# alimentacao.net
KiCad netlist of a schematic drawn in Altium Designer
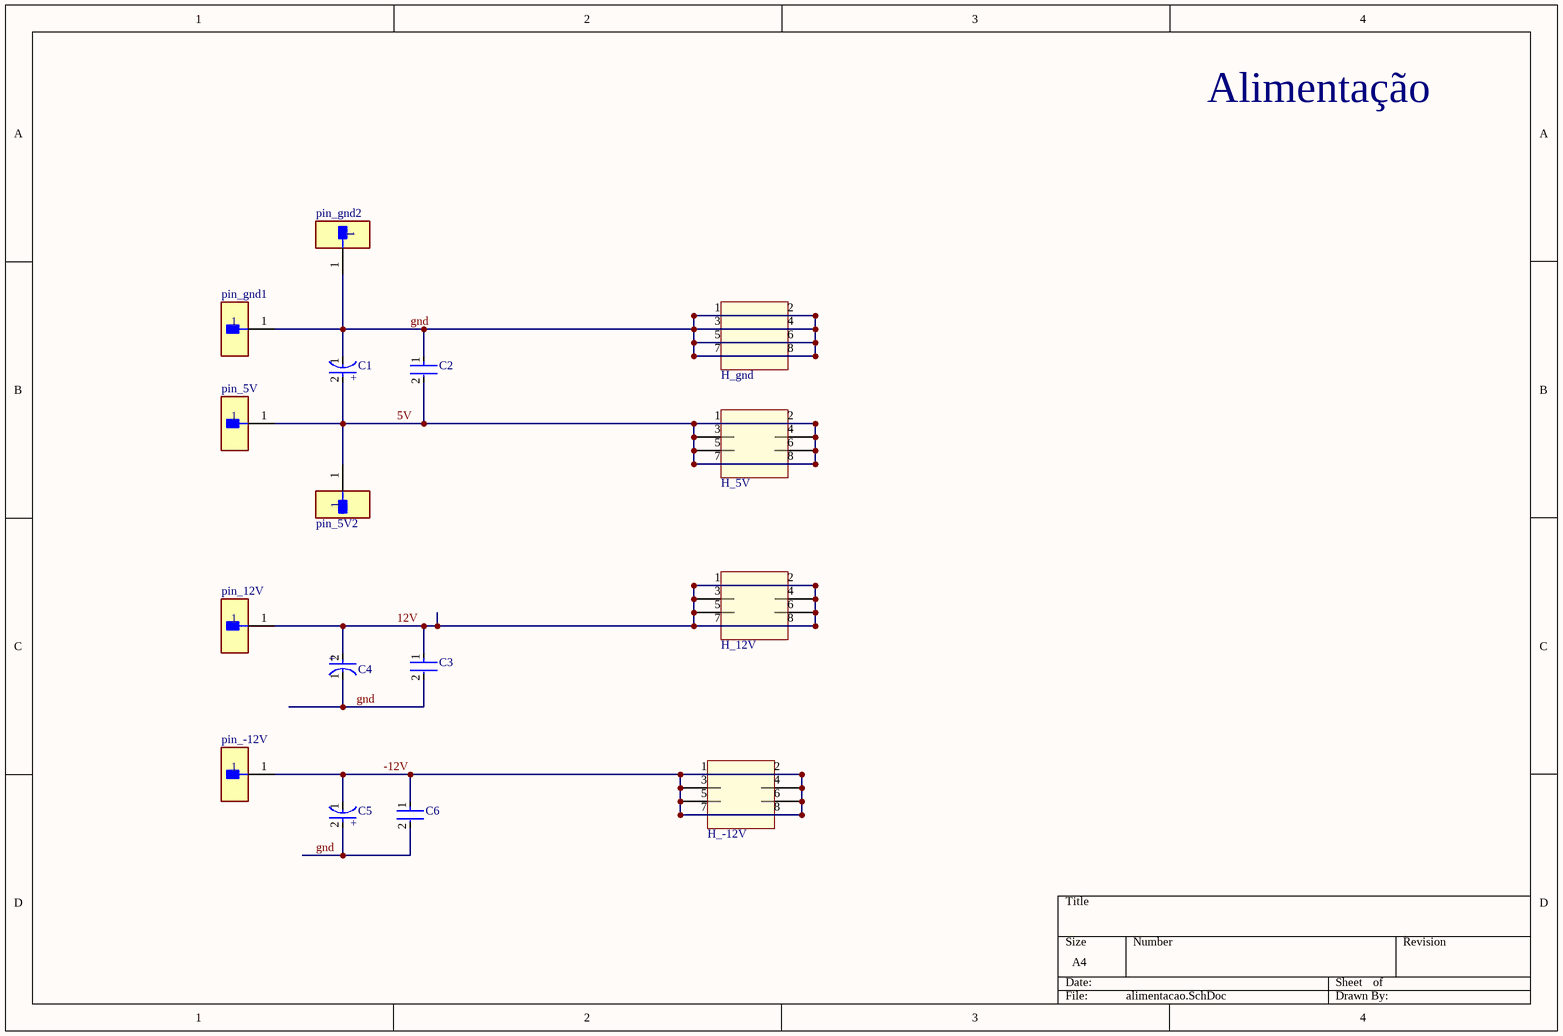
[diagram p0: alimentacao.SchDoc]

(export (version "E")
  (design (tool "Eeschema 10.0.6"))
  (components
    (comp (ref "C1")
      (value "EEU-FM1H101BJ")
      (footprint "FP-FM8-MFG")
      (description "CAP ALUM 100UF 20% 50V RADIAL")
      (fields (field (name "TOLERANCE") "20%"))
      (libsource (lib "Altium Content Vault") (part "203bc49f2ac43e59fd269a8c329ed05"))
    )
    (comp (ref "C2")
      (value "RCER71H335K3K1H03B")
      (footprint "FP-RCE3M1-MFG")
      (description "Cap Ceramic 3.3uF 50V X7R ±10% Radial 5mm +125°C Automotive Ammo Pack")
      (fields (field (name "TOLERANCE") "10%"))
      (libsource (lib "Altium Content Vault") (part "02cd4be3c70576c341d710602a673aa"))
    )
    (comp (ref "C3")
      (value "RCER71H335K3K1H03B")
      (footprint "FP-RCE3M1-MFG")
      (description "Cap Ceramic 3.3uF 50V X7R ±10% Radial 5mm +125°C Automotive Ammo Pack")
      (fields (field (name "TOLERANCE") "10%"))
      (libsource (lib "Altium Content Vault") (part "02cd4be3c70576c341d710602a673aa"))
    )
    (comp (ref "C4")
      (value "EEU-FM1H101BJ")
      (footprint "FP-FM8-MFG")
      (description "CAP ALUM 100UF 20% 50V RADIAL")
      (fields (field (name "TOLERANCE") "20%"))
      (libsource (lib "Altium Content Vault") (part "203bc49f2ac43e59fd269a8c329ed05"))
    )
    (comp (ref "C5")
      (value "EEU-FM1H101BJ")
      (footprint "FP-FM8-MFG")
      (description "CAP ALUM 100UF 20% 50V RADIAL")
      (fields (field (name "TOLERANCE") "20%"))
      (libsource (lib "Altium Content Vault") (part "203bc49f2ac43e59fd269a8c329ed05"))
    )
    (comp (ref "C6")
      (value "RCER71H335K3K1H03B")
      (footprint "FP-RCE3M1-MFG")
      (description "Cap Ceramic 3.3uF 50V X7R ±10% Radial 5mm +125°C Automotive Ammo Pack")
      (fields (field (name "TOLERANCE") "10%"))
      (libsource (lib "Altium Content Vault") (part "02cd4be3c70576c341d710602a673aa"))
    )
    (comp (ref "H_-12V")
      (value "header 2x4")
      (footprint "header 2x4")
      (description "header male 2x4")
      (libsource (lib "Schlib1") (part "header 2x4"))
    )
    (comp (ref "H_5V")
      (value "header 2x4")
      (footprint "header 2x4")
      (description "header male 2x4")
      (libsource (lib "Schlib1") (part "header 2x4"))
    )
    (comp (ref "H_12V")
      (value "header 2x4")
      (footprint "header 2x4")
      (description "header male 2x4")
      (libsource (lib "Schlib1") (part "header 2x4"))
    )
    (comp (ref "H_gnd")
      (value "header 2x4")
      (footprint "header 2x4")
      (description "header male 2x4")
      (libsource (lib "Schlib1") (part "header 2x4"))
    )
    (comp (ref "pin_-12V")
      (value "TSW-101-07-L-S")
      (footprint "FP-TSW-101-07-L-S-MFG")
      (description "CONN HEADER VERT 1POS")
      (libsource (lib "") (part "dd45045ce8184df9e99e12baf3f412c_1"))
    )
    (comp (ref "pin_5V")
      (value "TSW-101-07-L-S")
      (footprint "FP-TSW-101-07-L-S-MFG")
      (description "CONN HEADER VERT 1POS")
      (libsource (lib "") (part "dd45045ce8184df9e99e12baf3f412c_1"))
    )
    (comp (ref "pin_5V2")
      (value "TSW-101-07-L-S")
      (footprint "FP-TSW-101-07-L-S-MFG")
      (description "CONN HEADER VERT 1POS")
      (libsource (lib "") (part "dd45045ce8184df9e99e12baf3f412c_2"))
    )
    (comp (ref "pin_12V")
      (value "TSW-101-07-L-S")
      (footprint "FP-TSW-101-07-L-S-MFG")
      (description "CONN HEADER VERT 1POS")
      (libsource (lib "") (part "dd45045ce8184df9e99e12baf3f412c_1"))
    )
    (comp (ref "pin_gnd1")
      (value "TSW-101-07-L-S")
      (footprint "FP-TSW-101-07-L-S-MFG")
      (description "CONN HEADER VERT 1POS")
      (libsource (lib "") (part "dd45045ce8184df9e99e12baf3f412c_1"))
    )
    (comp (ref "pin_gnd2")
      (value "TSW-101-07-L-S")
      (footprint "FP-TSW-101-07-L-S-MFG")
      (description "CONN HEADER VERT 1POS")
      (libsource (lib "Altium Content Vault") (part "dd45045ce8184df9e99e12baf3f412c"))
    )
  )
  (nets
    (net (code "1") (name "/-12V") (class "Default")
      (node (ref "C5") (pin "1") (pinfunction "C_1") (pintype "passive"))
      (node (ref "C6") (pin "1") (pinfunction "1_1") (pintype "passive"))
      (node (ref "H_-12V") (pin "1") (pinfunction "1_1") (pintype "passive"))
      (node (ref "H_-12V") (pin "2") (pinfunction "2_2") (pintype "passive"))
      (node (ref "H_-12V") (pin "3") (pinfunction "3_3") (pintype "passive"))
      (node (ref "H_-12V") (pin "4") (pinfunction "4_4") (pintype "passive"))
      (node (ref "H_-12V") (pin "5") (pinfunction "5_5") (pintype "passive"))
      (node (ref "H_-12V") (pin "6") (pinfunction "6_6") (pintype "passive"))
      (node (ref "H_-12V") (pin "7") (pinfunction "7_7") (pintype "passive"))
      (node (ref "H_-12V") (pin "8") (pinfunction "8_8") (pintype "passive"))
      (node (ref "pin_-12V") (pin "1") (pinfunction "1_1") (pintype "passive"))
    )
    (net (code "2") (name "/5V") (class "Default")
      (node (ref "C1") (pin "2") (pinfunction "A_2") (pintype "passive"))
      (node (ref "C2") (pin "2") (pinfunction "2_2") (pintype "passive"))
      (node (ref "H_5V") (pin "1") (pinfunction "1_1") (pintype "passive"))
      (node (ref "H_5V") (pin "2") (pinfunction "2_2") (pintype "passive"))
      (node (ref "H_5V") (pin "3") (pinfunction "3_3") (pintype "passive"))
      (node (ref "H_5V") (pin "4") (pinfunction "4_4") (pintype "passive"))
      (node (ref "H_5V") (pin "5") (pinfunction "5_5") (pintype "passive"))
      (node (ref "H_5V") (pin "6") (pinfunction "6_6") (pintype "passive"))
      (node (ref "H_5V") (pin "7") (pinfunction "7_7") (pintype "passive"))
      (node (ref "H_5V") (pin "8") (pinfunction "8_8") (pintype "passive"))
      (node (ref "pin_5V") (pin "1") (pinfunction "1_1") (pintype "passive"))
      (node (ref "pin_5V2") (pin "1") (pinfunction "1_1") (pintype "passive"))
    )
    (net (code "3") (name "/12V") (class "Default")
      (node (ref "C3") (pin "1") (pinfunction "1_1") (pintype "passive"))
      (node (ref "C4") (pin "2") (pinfunction "A_2") (pintype "passive"))
      (node (ref "H_12V") (pin "1") (pinfunction "1_1") (pintype "passive"))
      (node (ref "H_12V") (pin "2") (pinfunction "2_2") (pintype "passive"))
      (node (ref "H_12V") (pin "3") (pinfunction "3_3") (pintype "passive"))
      (node (ref "H_12V") (pin "4") (pinfunction "4_4") (pintype "passive"))
      (node (ref "H_12V") (pin "5") (pinfunction "5_5") (pintype "passive"))
      (node (ref "H_12V") (pin "6") (pinfunction "6_6") (pintype "passive"))
      (node (ref "H_12V") (pin "7") (pinfunction "7_7") (pintype "passive"))
      (node (ref "H_12V") (pin "8") (pinfunction "8_8") (pintype "passive"))
      (node (ref "pin_12V") (pin "1") (pinfunction "1_1") (pintype "passive"))
    )
    (net (code "4") (name "/gnd") (class "Default")
      (node (ref "C1") (pin "1") (pinfunction "C_1") (pintype "passive"))
      (node (ref "C2") (pin "1") (pinfunction "1_1") (pintype "passive"))
      (node (ref "C3") (pin "2") (pinfunction "2_2") (pintype "passive"))
      (node (ref "C4") (pin "1") (pinfunction "C_1") (pintype "passive"))
      (node (ref "C5") (pin "2") (pinfunction "A_2") (pintype "passive"))
      (node (ref "C6") (pin "2") (pinfunction "2_2") (pintype "passive"))
      (node (ref "H_gnd") (pin "1") (pinfunction "1_1") (pintype "passive"))
      (node (ref "H_gnd") (pin "2") (pinfunction "2_2") (pintype "passive"))
      (node (ref "H_gnd") (pin "3") (pinfunction "3_3") (pintype "passive"))
      (node (ref "H_gnd") (pin "4") (pinfunction "4_4") (pintype "passive"))
      (node (ref "H_gnd") (pin "5") (pinfunction "5_5") (pintype "passive"))
      (node (ref "H_gnd") (pin "6") (pinfunction "6_6") (pintype "passive"))
      (node (ref "H_gnd") (pin "7") (pinfunction "7_7") (pintype "passive"))
      (node (ref "H_gnd") (pin "8") (pinfunction "8_8") (pintype "passive"))
      (node (ref "pin_gnd1") (pin "1") (pinfunction "1_1") (pintype "passive"))
      (node (ref "pin_gnd2") (pin "1") (pinfunction "1_1") (pintype "passive"))
    )
  )
)
